# LED_BAT_breakout.net
KiCad netlist of a schematic drawn in Altium Designer
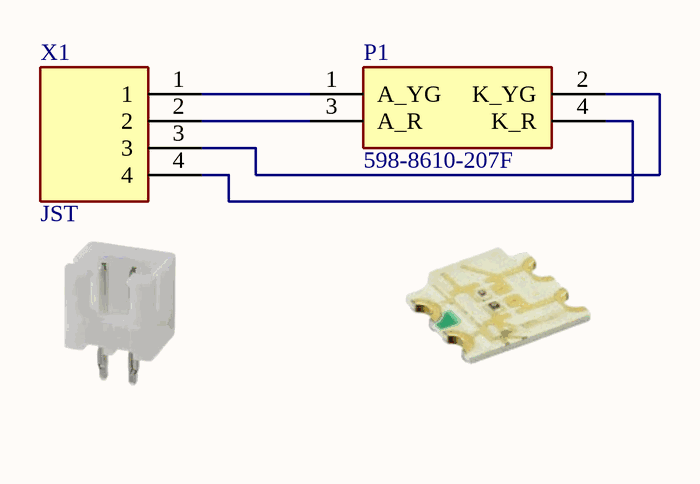
[diagram p0: LED_BAT_breakout.SchDoc]

(export (version "E")
  (design (tool "Eeschema 10.0.6"))
  (components
    (comp (ref "P1")
      (value "598-8610-207F")
      (footprint "SamacSys:5988610207F")
      (description "LED")
      (fields (field (name "MOUSER PART NUMBER") "645-598-8610-207F"))
      (libsource (lib "SamacSys") (part "598-8610-207F"))
    )
    (comp (ref "X1")
      (value "JST")
      (footprint "Header 4pin 2,54mm")
      (description "Connector")
      (fields (field (name "MANUFACTURER_PART_NUMBER") "B4B-XH-AM (LF)(SN)"))
      (libsource (lib "*") (part "B4B-XH-AM__LF__SN_"))
    )
  )
  (nets
    (net (code "1") (name "Net-(P1-A_R)") (class "Default")
      (node (ref "P1") (pin "3") (pinfunction "A_R_3") (pintype "passive"))
      (node (ref "X1") (pin "2") (pinfunction "2_2") (pintype "passive"))
    )
    (net (code "2") (name "Net-(P1-A_YG)") (class "Default")
      (node (ref "P1") (pin "1") (pinfunction "A_YG_1") (pintype "passive"))
      (node (ref "X1") (pin "1") (pinfunction "1_1") (pintype "passive"))
    )
    (net (code "3") (name "Net-(P1-K_R)") (class "Default")
      (node (ref "P1") (pin "4") (pinfunction "K_R_4") (pintype "passive"))
      (node (ref "X1") (pin "4") (pinfunction "4_4") (pintype "passive"))
    )
    (net (code "4") (name "Net-(P1-K_YG)") (class "Default")
      (node (ref "P1") (pin "2") (pinfunction "K_YG_2") (pintype "passive"))
      (node (ref "X1") (pin "3") (pinfunction "3_3") (pintype "passive"))
    )
  )
)
